# RobotBaseModule.net
KiCad netlist of a schematic drawn in EAGLE
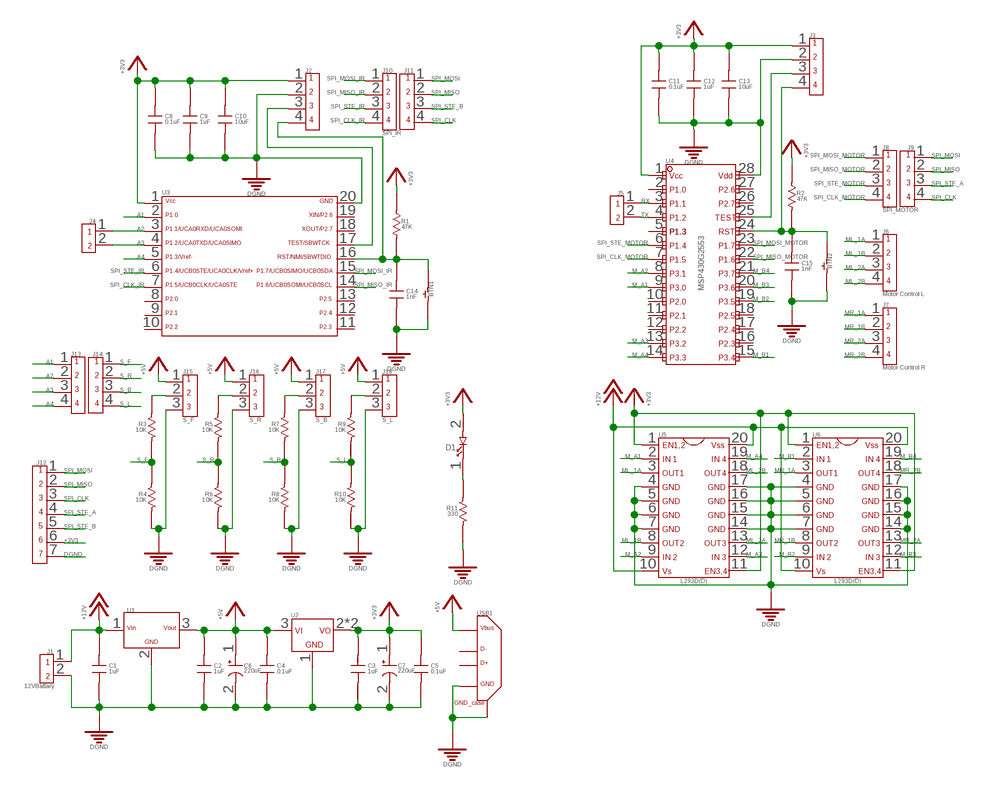
[diagram p0: schematic, sheet 1]

(export (version "E")
  (design (tool "Eeschema 10.0.6"))
  (components
    (comp (ref "BTN1")
      (value "BTN_NORMAL_OFF_6_3.5_SMD")
      (footprint "eagle-import:BTN_6_3.5_SMD")
      (libsource (lib "eagle-import") (part "BTN_NORMAL_OFF_6_3.5_SMD"))
    )
    (comp (ref "BTN2")
      (value "BTN_NORMAL_OFF_6_3.5_SMD")
      (footprint "eagle-import:BTN_6_3.5_SMD")
      (libsource (lib "eagle-import") (part "BTN_NORMAL_OFF_6_3.5_SMD"))
    )
    (comp (ref "C1")
      (value "1uF")
      (footprint "eagle-import:0805")
      (libsource (lib "eagle-import") (part "CAPACITOR_FIXED_0805"))
    )
    (comp (ref "C2")
      (value "1uF")
      (footprint "eagle-import:0805")
      (libsource (lib "eagle-import") (part "CAPACITOR_FIXED_0805"))
    )
    (comp (ref "C3")
      (value "1uF")
      (footprint "eagle-import:0805")
      (libsource (lib "eagle-import") (part "CAPACITOR_FIXED_0805"))
    )
    (comp (ref "C4")
      (value "0.1uF")
      (footprint "eagle-import:0805")
      (libsource (lib "eagle-import") (part "CAPACITOR_FIXED_0805"))
    )
    (comp (ref "C5")
      (value "0.1uF")
      (footprint "eagle-import:0805")
      (libsource (lib "eagle-import") (part "CAPACITOR_FIXED_0805"))
    )
    (comp (ref "C6")
      (value "220uF")
      (footprint "eagle-import:CAP_830_830")
      (libsource (lib "eagle-import") (part "CAPACITOR_POLARIZED_830_830"))
    )
    (comp (ref "C7")
      (value "220uF")
      (footprint "eagle-import:CAP_830_830")
      (libsource (lib "eagle-import") (part "CAPACITOR_POLARIZED_830_830"))
    )
    (comp (ref "C8")
      (value "0.1uF")
      (footprint "eagle-import:0805")
      (libsource (lib "eagle-import") (part "CAPACITOR_FIXED_0805"))
    )
    (comp (ref "C9")
      (value "1uF")
      (footprint "eagle-import:0805")
      (libsource (lib "eagle-import") (part "CAPACITOR_FIXED_0805"))
    )
    (comp (ref "C10")
      (value "10uF")
      (footprint "eagle-import:0805")
      (libsource (lib "eagle-import") (part "CAPACITOR_FIXED_0805"))
    )
    (comp (ref "C11")
      (value "0.1uF")
      (footprint "eagle-import:0805")
      (libsource (lib "eagle-import") (part "CAPACITOR_FIXED_0805"))
    )
    (comp (ref "C12")
      (value "1uF")
      (footprint "eagle-import:0805")
      (libsource (lib "eagle-import") (part "CAPACITOR_FIXED_0805"))
    )
    (comp (ref "C13")
      (value "10uF")
      (footprint "eagle-import:0805")
      (libsource (lib "eagle-import") (part "CAPACITOR_FIXED_0805"))
    )
    (comp (ref "C14")
      (value "1nF")
      (footprint "eagle-import:0805")
      (libsource (lib "eagle-import") (part "CAPACITOR_FIXED_0805"))
    )
    (comp (ref "C15")
      (value "1nF")
      (footprint "eagle-import:0805")
      (libsource (lib "eagle-import") (part "CAPACITOR_FIXED_0805"))
    )
    (comp (ref "D1")
      (value "LED_0805")
      (footprint "eagle-import:0805DIODE")
      (libsource (lib "eagle-import") (part "LED_0805"))
    )
    (comp (ref "J1")
      (value "12VBattary")
      (footprint "eagle-import:2PIN_TERMBLOCK_PITCH5.08MM")
      (libsource (lib "eagle-import") (part "2PIN_TERMBLOCK_PITCH5.08MM"))
    )
    (comp (ref "J2")
      (value "4PIN_HEADER_VERT_PITCH2.54MM_TH")
      (footprint "eagle-import:4PIN_HEADER_VERT_PITCH2.54MM_TH")
      (libsource (lib "eagle-import") (part "4PIN_HEADER_VERT_PITCH2.54MM_TH"))
    )
    (comp (ref "J3")
      (value "4PIN_HEADER_VERT_PITCH2.54MM_TH")
      (footprint "eagle-import:4PIN_HEADER_VERT_PITCH2.54MM_TH")
      (libsource (lib "eagle-import") (part "4PIN_HEADER_VERT_PITCH2.54MM_TH"))
    )
    (comp (ref "J4")
      (value "2PIN_HEADER_PITCH2.54MM_TH")
      (footprint "eagle-import:2PIN_HEADER_PITCH2.54MM_TH")
      (libsource (lib "eagle-import") (part "2PIN_HEADER_PITCH2.54MM_TH"))
    )
    (comp (ref "J5")
      (value "2PIN_HEADER_PITCH2.54MM_TH")
      (footprint "eagle-import:2PIN_HEADER_PITCH2.54MM_TH")
      (libsource (lib "eagle-import") (part "2PIN_HEADER_PITCH2.54MM_TH"))
    )
    (comp (ref "J6")
      (value "Motor Control L")
      (footprint "eagle-import:4PIN_HEADER_VERT_PITCH2.54MM_TH")
      (libsource (lib "eagle-import") (part "4PIN_HEADER_VERT_PITCH2.54MM_TH"))
    )
    (comp (ref "J7")
      (value "Motor Control R")
      (footprint "eagle-import:4PIN_HEADER_VERT_PITCH2.54MM_TH")
      (libsource (lib "eagle-import") (part "4PIN_HEADER_VERT_PITCH2.54MM_TH"))
    )
    (comp (ref "J8")
      (value "SPI_MOTOR")
      (footprint "eagle-import:4PIN_HEADER_PITCH2.54MM_TH")
      (libsource (lib "eagle-import") (part "4PIN_HEADER_PITCH2.54MM_TH"))
    )
    (comp (ref "J9")
      (value "4PIN_HEADER_PITCH2.54MM_TH")
      (footprint "eagle-import:4PIN_HEADER_PITCH2.54MM_TH")
      (libsource (lib "eagle-import") (part "4PIN_HEADER_PITCH2.54MM_TH"))
    )
    (comp (ref "J10")
      (value "SPI_IR")
      (footprint "eagle-import:4PIN_HEADER_PITCH2.54MM_TH")
      (libsource (lib "eagle-import") (part "4PIN_HEADER_PITCH2.54MM_TH"))
    )
    (comp (ref "J11")
      (value "4PIN_HEADER_PITCH2.54MM_TH")
      (footprint "eagle-import:4PIN_HEADER_PITCH2.54MM_TH")
      (libsource (lib "eagle-import") (part "4PIN_HEADER_PITCH2.54MM_TH"))
    )
    (comp (ref "J12")
      (value "7PIN_HEADER_VERT_PITCH2.54MM_TH")
      (footprint "eagle-import:7PIN_HEADER_VERT_PITCH2.54MM_TH")
      (libsource (lib "eagle-import") (part "7PIN_HEADER_VERT_PITCH2.54MM_TH"))
    )
    (comp (ref "J13")
      (value "4PIN_HEADER_PITCH2.54MM_TH")
      (footprint "eagle-import:4PIN_HEADER_PITCH2.54MM_TH")
      (libsource (lib "eagle-import") (part "4PIN_HEADER_PITCH2.54MM_TH"))
    )
    (comp (ref "J14")
      (value "4PIN_HEADER_PITCH2.54MM_TH")
      (footprint "eagle-import:4PIN_HEADER_PITCH2.54MM_TH")
      (libsource (lib "eagle-import") (part "4PIN_HEADER_PITCH2.54MM_TH"))
    )
    (comp (ref "J15")
      (value "S_F")
      (footprint "eagle-import:3PIN_HEADER_VERT_PITCH2.54MM_TH")
      (libsource (lib "eagle-import") (part "3PIN_HEADER_VERT_PITCH2.54MM_TH"))
    )
    (comp (ref "J16")
      (value "S_R")
      (footprint "eagle-import:3PIN_HEADER_VERT_PITCH2.54MM_TH")
      (libsource (lib "eagle-import") (part "3PIN_HEADER_VERT_PITCH2.54MM_TH"))
    )
    (comp (ref "J17")
      (value "S_B")
      (footprint "eagle-import:3PIN_HEADER_VERT_PITCH2.54MM_TH")
      (libsource (lib "eagle-import") (part "3PIN_HEADER_VERT_PITCH2.54MM_TH"))
    )
    (comp (ref "J18")
      (value "S_L")
      (footprint "eagle-import:3PIN_HEADER_VERT_PITCH2.54MM_TH")
      (libsource (lib "eagle-import") (part "3PIN_HEADER_VERT_PITCH2.54MM_TH"))
    )
    (comp (ref "R1")
      (value "47K")
      (footprint "eagle-import:0805")
      (libsource (lib "eagle-import") (part "RESISTOR_0805"))
    )
    (comp (ref "R2")
      (value "47K")
      (footprint "eagle-import:0805")
      (libsource (lib "eagle-import") (part "RESISTOR_0805"))
    )
    (comp (ref "R3")
      (value "10K")
      (footprint "eagle-import:0805")
      (libsource (lib "eagle-import") (part "RESISTOR_0805"))
    )
    (comp (ref "R4")
      (value "10K")
      (footprint "eagle-import:0805")
      (libsource (lib "eagle-import") (part "RESISTOR_0805"))
    )
    (comp (ref "R5")
      (value "10K")
      (footprint "eagle-import:0805")
      (libsource (lib "eagle-import") (part "RESISTOR_0805"))
    )
    (comp (ref "R6")
      (value "10K")
      (footprint "eagle-import:0805")
      (libsource (lib "eagle-import") (part "RESISTOR_0805"))
    )
    (comp (ref "R7")
      (value "10K")
      (footprint "eagle-import:0805")
      (libsource (lib "eagle-import") (part "RESISTOR_0805"))
    )
    (comp (ref "R8")
      (value "10K")
      (footprint "eagle-import:0805")
      (libsource (lib "eagle-import") (part "RESISTOR_0805"))
    )
    (comp (ref "R9")
      (value "10K")
      (footprint "eagle-import:0805")
      (libsource (lib "eagle-import") (part "RESISTOR_0805"))
    )
    (comp (ref "R10")
      (value "10K")
      (footprint "eagle-import:0805")
      (libsource (lib "eagle-import") (part "RESISTOR_0805"))
    )
    (comp (ref "R11")
      (value "330")
      (footprint "eagle-import:0805")
      (libsource (lib "eagle-import") (part "RESISTOR_0805"))
    )
    (comp (ref "U1")
      (value "V78-2000R")
      (footprint "eagle-import:V78-2000R")
      (libsource (lib "eagle-import") (part "V78-2000R"))
    )
    (comp (ref "U2")
      (value "LM1117_SOT-223-4")
      (footprint "eagle-import:SOT-233-4")
      (libsource (lib "eagle-import") (part "LM1117_SOT-223-4"))
    )
    (comp (ref "U3")
      (value "MSP430G2X53/G2X13_SSOP20")
      (footprint "eagle-import:SSOP-20")
      (libsource (lib "eagle-import") (part "MSP430G2X53/G2X13_SSOP20"))
    )
    (comp (ref "U4")
      (value "MSP430G2553")
      (footprint "eagle-import:TSSOP-28")
      (libsource (lib "eagle-import") (part "MSP430G2553_24IO_28PIN_TSSOP"))
    )
    (comp (ref "U5")
      (value "L293D(D)_ST_SMD")
      (footprint "eagle-import:SOIC_20")
      (libsource (lib "eagle-import") (part "L293D(D)_ST_SMD"))
    )
    (comp (ref "U6")
      (value "L293D(D)_ST_SMD")
      (footprint "eagle-import:SOIC_20")
      (libsource (lib "eagle-import") (part "L293D(D)_ST_SMD"))
    )
    (comp (ref "USB1")
      (value "USB-1.X/2.0-STANDARDTYPEA-TH")
      (footprint "eagle-import:USB-A-TH")
      (libsource (lib "eagle-import") (part "USB-1.X/2.0-STANDARDTYPEA-TH"))
    )
  )
  (nets
    (net (code "1") (name "+3V3") (class "Default")
      (node (ref "C10") (pin "1") (pinfunction "1_1") (pintype "passive"))
      (node (ref "C11") (pin "1") (pinfunction "1_1") (pintype "passive"))
      (node (ref "C12") (pin "1") (pinfunction "1_1") (pintype "passive"))
      (node (ref "C13") (pin "1") (pinfunction "1_1") (pintype "passive"))
      (node (ref "C3") (pin "1") (pinfunction "1_1") (pintype "passive"))
      (node (ref "C5") (pin "1") (pinfunction "1_1") (pintype "passive"))
      (node (ref "C7") (pin "1") (pinfunction "1_1") (pintype "passive"))
      (node (ref "C8") (pin "1") (pinfunction "1_1") (pintype "passive"))
      (node (ref "C9") (pin "1") (pinfunction "1_1") (pintype "passive"))
      (node (ref "D1") (pin "2") (pinfunction "2_2") (pintype "passive"))
      (node (ref "J12") (pin "6") (pinfunction "6_6") (pintype "passive"))
      (node (ref "J2") (pin "1") (pinfunction "1_1") (pintype "passive"))
      (node (ref "J3") (pin "1") (pinfunction "1_1") (pintype "passive"))
      (node (ref "R1") (pin "1") (pinfunction "1_1") (pintype "passive"))
      (node (ref "R2") (pin "1") (pinfunction "1_1") (pintype "passive"))
      (node (ref "U2") (pin "2") (pinfunction "VOUT_2") (pintype "passive"))
      (node (ref "U2") (pin "4") (pinfunction "VOUT_4") (pintype "passive"))
      (node (ref "U3") (pin "1") (pinfunction "1_1") (pintype "passive"))
      (node (ref "U4") (pin "1") (pinfunction "1_1") (pintype "passive"))
      (node (ref "U5") (pin "1") (pinfunction "1_1") (pintype "passive"))
      (node (ref "U5") (pin "11") (pinfunction "11_11") (pintype "passive"))
      (node (ref "U6") (pin "1") (pinfunction "1_1") (pintype "passive"))
      (node (ref "U6") (pin "11") (pinfunction "11_11") (pintype "passive"))
    )
    (net (code "2") (name "+5V") (class "Default")
      (node (ref "C2") (pin "1") (pinfunction "1_1") (pintype "passive"))
      (node (ref "C4") (pin "1") (pinfunction "1_1") (pintype "passive"))
      (node (ref "C6") (pin "1") (pinfunction "1_1") (pintype "passive"))
      (node (ref "J15") (pin "1") (pinfunction "1_1") (pintype "passive"))
      (node (ref "J16") (pin "1") (pinfunction "1_1") (pintype "passive"))
      (node (ref "J17") (pin "1") (pinfunction "1_1") (pintype "passive"))
      (node (ref "J18") (pin "1") (pinfunction "1_1") (pintype "passive"))
      (node (ref "U1") (pin "3") (pinfunction "VOUT_3") (pintype "passive"))
      (node (ref "U2") (pin "3") (pinfunction "VIN_3") (pintype "passive"))
      (node (ref "USB1") (pin "1") (pinfunction "VBUS_1") (pintype "passive"))
    )
    (net (code "3") (name "+12V") (class "Default")
      (node (ref "C1") (pin "1") (pinfunction "1_1") (pintype "passive"))
      (node (ref "J1") (pin "1") (pinfunction "1_1") (pintype "passive"))
      (node (ref "U1") (pin "1") (pinfunction "VIN_1") (pintype "passive"))
      (node (ref "U5") (pin "10") (pinfunction "10_10") (pintype "passive"))
      (node (ref "U5") (pin "20") (pinfunction "20_20") (pintype "passive"))
      (node (ref "U6") (pin "10") (pinfunction "10_10") (pintype "passive"))
      (node (ref "U6") (pin "20") (pinfunction "20_20") (pintype "passive"))
    )
    (net (code "4") (name "/A1") (class "Default")
      (node (ref "J13") (pin "1") (pinfunction "1_1") (pintype "passive"))
      (node (ref "U3") (pin "2") (pinfunction "2_2") (pintype "passive"))
    )
    (net (code "5") (name "/A2") (class "Default")
      (node (ref "J13") (pin "2") (pinfunction "2_2") (pintype "passive"))
      (node (ref "J4") (pin "1") (pinfunction "1_1") (pintype "passive"))
      (node (ref "U3") (pin "3") (pinfunction "3_3") (pintype "passive"))
    )
    (net (code "6") (name "/A3") (class "Default")
      (node (ref "J13") (pin "3") (pinfunction "3_3") (pintype "passive"))
      (node (ref "J4") (pin "2") (pinfunction "2_2") (pintype "passive"))
      (node (ref "U3") (pin "4") (pinfunction "4_4") (pintype "passive"))
    )
    (net (code "7") (name "/A4") (class "Default")
      (node (ref "J13") (pin "4") (pinfunction "4_4") (pintype "passive"))
      (node (ref "U3") (pin "5") (pinfunction "5_5") (pintype "passive"))
    )
    (net (code "8") (name "/ML_1A") (class "Default")
      (node (ref "J6") (pin "1") (pinfunction "1_1") (pintype "passive"))
      (node (ref "U5") (pin "3") (pinfunction "3_3") (pintype "passive"))
    )
    (net (code "9") (name "/ML_1B") (class "Default")
      (node (ref "J6") (pin "2") (pinfunction "2_2") (pintype "passive"))
      (node (ref "U5") (pin "8") (pinfunction "8_8") (pintype "passive"))
    )
    (net (code "10") (name "/ML_2A") (class "Default")
      (node (ref "J6") (pin "3") (pinfunction "3_3") (pintype "passive"))
      (node (ref "U5") (pin "13") (pinfunction "13_13") (pintype "passive"))
    )
    (net (code "11") (name "/ML_2B") (class "Default")
      (node (ref "J6") (pin "4") (pinfunction "4_4") (pintype "passive"))
      (node (ref "U5") (pin "18") (pinfunction "18_18") (pintype "passive"))
    )
    (net (code "12") (name "/MR_1A") (class "Default")
      (node (ref "J7") (pin "1") (pinfunction "1_1") (pintype "passive"))
      (node (ref "U6") (pin "3") (pinfunction "3_3") (pintype "passive"))
    )
    (net (code "13") (name "/MR_1B") (class "Default")
      (node (ref "J7") (pin "2") (pinfunction "2_2") (pintype "passive"))
      (node (ref "U6") (pin "8") (pinfunction "8_8") (pintype "passive"))
    )
    (net (code "14") (name "/MR_2A") (class "Default")
      (node (ref "J7") (pin "3") (pinfunction "3_3") (pintype "passive"))
      (node (ref "U6") (pin "13") (pinfunction "13_13") (pintype "passive"))
    )
    (net (code "15") (name "/MR_2B") (class "Default")
      (node (ref "J7") (pin "4") (pinfunction "4_4") (pintype "passive"))
      (node (ref "U6") (pin "18") (pinfunction "18_18") (pintype "passive"))
    )
    (net (code "16") (name "/M_A1") (class "Default")
      (node (ref "U4") (pin "9") (pinfunction "9_9") (pintype "passive"))
      (node (ref "U5") (pin "2") (pinfunction "2_2") (pintype "passive"))
    )
    (net (code "17") (name "/M_A2") (class "Default")
      (node (ref "U4") (pin "8") (pinfunction "8_8") (pintype "passive"))
      (node (ref "U5") (pin "9") (pinfunction "9_9") (pintype "passive"))
    )
    (net (code "18") (name "/M_A3") (class "Default")
      (node (ref "U4") (pin "13") (pinfunction "13_13") (pintype "passive"))
      (node (ref "U5") (pin "12") (pinfunction "12_12") (pintype "passive"))
    )
    (net (code "19") (name "/M_A4") (class "Default")
      (node (ref "U4") (pin "14") (pinfunction "14_14") (pintype "passive"))
      (node (ref "U5") (pin "19") (pinfunction "19_19") (pintype "passive"))
    )
    (net (code "20") (name "/M_B1") (class "Default")
      (node (ref "U4") (pin "15") (pinfunction "15_15") (pintype "passive"))
      (node (ref "U6") (pin "2") (pinfunction "2_2") (pintype "passive"))
    )
    (net (code "21") (name "/M_B2") (class "Default")
      (node (ref "U4") (pin "19") (pinfunction "19_19") (pintype "passive"))
      (node (ref "U6") (pin "9") (pinfunction "9_9") (pintype "passive"))
    )
    (net (code "22") (name "/M_B3") (class "Default")
      (node (ref "U4") (pin "20") (pinfunction "20_20") (pintype "passive"))
      (node (ref "U6") (pin "12") (pinfunction "12_12") (pintype "passive"))
    )
    (net (code "23") (name "/M_B4") (class "Default")
      (node (ref "U4") (pin "21") (pinfunction "21_21") (pintype "passive"))
      (node (ref "U6") (pin "19") (pinfunction "19_19") (pintype "passive"))
    )
    (net (code "24") (name "/RX") (class "Default")
      (node (ref "J5") (pin "1") (pinfunction "1_1") (pintype "passive"))
      (node (ref "U4") (pin "3") (pinfunction "3_3") (pintype "passive"))
    )
    (net (code "25") (name "/SPI_CLK") (class "Default")
      (node (ref "J11") (pin "4") (pinfunction "4_4") (pintype "passive"))
      (node (ref "J12") (pin "3") (pinfunction "3_3") (pintype "passive"))
      (node (ref "J9") (pin "4") (pinfunction "4_4") (pintype "passive"))
    )
    (net (code "26") (name "/SPI_CLK_IR") (class "Default")
      (node (ref "J10") (pin "4") (pinfunction "4_4") (pintype "passive"))
      (node (ref "U3") (pin "7") (pinfunction "7_7") (pintype "passive"))
    )
    (net (code "27") (name "/SPI_CLK_MOTOR") (class "Default")
      (node (ref "J8") (pin "4") (pinfunction "4_4") (pintype "passive"))
      (node (ref "U4") (pin "7") (pinfunction "7_7") (pintype "passive"))
    )
    (net (code "28") (name "/SPI_MISO") (class "Default")
      (node (ref "J11") (pin "2") (pinfunction "2_2") (pintype "passive"))
      (node (ref "J12") (pin "2") (pinfunction "2_2") (pintype "passive"))
      (node (ref "J9") (pin "2") (pinfunction "2_2") (pintype "passive"))
    )
    (net (code "29") (name "/SPI_MISO_IR") (class "Default")
      (node (ref "J10") (pin "2") (pinfunction "2_2") (pintype "passive"))
      (node (ref "U3") (pin "14") (pinfunction "14_14") (pintype "passive"))
    )
    (net (code "30") (name "/SPI_MISO_MOTOR") (class "Default")
      (node (ref "J8") (pin "2") (pinfunction "2_2") (pintype "passive"))
      (node (ref "U4") (pin "22") (pinfunction "22_22") (pintype "passive"))
    )
    (net (code "31") (name "/SPI_MOSI") (class "Default")
      (node (ref "J11") (pin "1") (pinfunction "1_1") (pintype "passive"))
      (node (ref "J12") (pin "1") (pinfunction "1_1") (pintype "passive"))
      (node (ref "J9") (pin "1") (pinfunction "1_1") (pintype "passive"))
    )
    (net (code "32") (name "/SPI_MOSI_IR") (class "Default")
      (node (ref "J10") (pin "1") (pinfunction "1_1") (pintype "passive"))
      (node (ref "U3") (pin "15") (pinfunction "15_15") (pintype "passive"))
    )
    (net (code "33") (name "/SPI_MOSI_MOTOR") (class "Default")
      (node (ref "J8") (pin "1") (pinfunction "1_1") (pintype "passive"))
      (node (ref "U4") (pin "23") (pinfunction "23_23") (pintype "passive"))
    )
    (net (code "34") (name "/SPI_STE_A") (class "Default")
      (node (ref "J12") (pin "4") (pinfunction "4_4") (pintype "passive"))
      (node (ref "J9") (pin "3") (pinfunction "3_3") (pintype "passive"))
    )
    (net (code "35") (name "/SPI_STE_B") (class "Default")
      (node (ref "J11") (pin "3") (pinfunction "3_3") (pintype "passive"))
      (node (ref "J12") (pin "5") (pinfunction "5_5") (pintype "passive"))
    )
    (net (code "36") (name "/SPI_STE_IR") (class "Default")
      (node (ref "J10") (pin "3") (pinfunction "3_3") (pintype "passive"))
      (node (ref "U3") (pin "6") (pinfunction "6_6") (pintype "passive"))
    )
    (net (code "37") (name "/SPI_STE_MOTOR") (class "Default")
      (node (ref "J8") (pin "3") (pinfunction "3_3") (pintype "passive"))
      (node (ref "U4") (pin "6") (pinfunction "6_6") (pintype "passive"))
    )
    (net (code "38") (name "/S_B") (class "Default")
      (node (ref "J14") (pin "3") (pinfunction "3_3") (pintype "passive"))
      (node (ref "R7") (pin "2") (pinfunction "2_2") (pintype "passive"))
      (node (ref "R8") (pin "1") (pinfunction "1_1") (pintype "passive"))
    )
    (net (code "39") (name "/S_F") (class "Default")
      (node (ref "J14") (pin "1") (pinfunction "1_1") (pintype "passive"))
      (node (ref "R3") (pin "2") (pinfunction "2_2") (pintype "passive"))
      (node (ref "R4") (pin "1") (pinfunction "1_1") (pintype "passive"))
    )
    (net (code "40") (name "/S_L") (class "Default")
      (node (ref "J14") (pin "4") (pinfunction "4_4") (pintype "passive"))
      (node (ref "R10") (pin "1") (pinfunction "1_1") (pintype "passive"))
      (node (ref "R9") (pin "2") (pinfunction "2_2") (pintype "passive"))
    )
    (net (code "41") (name "/S_R") (class "Default")
      (node (ref "J14") (pin "2") (pinfunction "2_2") (pintype "passive"))
      (node (ref "R5") (pin "2") (pinfunction "2_2") (pintype "passive"))
      (node (ref "R6") (pin "1") (pinfunction "1_1") (pintype "passive"))
    )
    (net (code "42") (name "/TX") (class "Default")
      (node (ref "J5") (pin "2") (pinfunction "2_2") (pintype "passive"))
      (node (ref "U4") (pin "4") (pinfunction "4_4") (pintype "passive"))
    )
    (net (code "43") (name "DGND") (class "Default")
      (node (ref "BTN1") (pin "2") (pinfunction "2_2") (pintype "passive"))
      (node (ref "BTN2") (pin "2") (pinfunction "2_2") (pintype "passive"))
      (node (ref "C1") (pin "2") (pinfunction "2_2") (pintype "passive"))
      (node (ref "C10") (pin "2") (pinfunction "2_2") (pintype "passive"))
      (node (ref "C11") (pin "2") (pinfunction "2_2") (pintype "passive"))
      (node (ref "C12") (pin "2") (pinfunction "2_2") (pintype "passive"))
      (node (ref "C13") (pin "2") (pinfunction "2_2") (pintype "passive"))
      (node (ref "C14") (pin "2") (pinfunction "2_2") (pintype "passive"))
      (node (ref "C15") (pin "2") (pinfunction "2_2") (pintype "passive"))
      (node (ref "C2") (pin "2") (pinfunction "2_2") (pintype "passive"))
      (node (ref "C3") (pin "2") (pinfunction "2_2") (pintype "passive"))
      (node (ref "C4") (pin "2") (pinfunction "2_2") (pintype "passive"))
      (node (ref "C5") (pin "2") (pinfunction "2_2") (pintype "passive"))
      (node (ref "C6") (pin "2") (pinfunction "2_2") (pintype "passive"))
      (node (ref "C7") (pin "2") (pinfunction "2_2") (pintype "passive"))
      (node (ref "C8") (pin "2") (pinfunction "2_2") (pintype "passive"))
      (node (ref "C9") (pin "2") (pinfunction "2_2") (pintype "passive"))
      (node (ref "J1") (pin "2") (pinfunction "2_2") (pintype "passive"))
      (node (ref "J12") (pin "7") (pinfunction "7_7") (pintype "passive"))
      (node (ref "J15") (pin "3") (pinfunction "3_3") (pintype "passive"))
      (node (ref "J16") (pin "3") (pinfunction "3_3") (pintype "passive"))
      (node (ref "J17") (pin "3") (pinfunction "3_3") (pintype "passive"))
      (node (ref "J18") (pin "3") (pinfunction "3_3") (pintype "passive"))
      (node (ref "J2") (pin "2") (pinfunction "2_2") (pintype "passive"))
      (node (ref "J3") (pin "2") (pinfunction "2_2") (pintype "passive"))
      (node (ref "R10") (pin "2") (pinfunction "2_2") (pintype "passive"))
      (node (ref "R11") (pin "2") (pinfunction "2_2") (pintype "passive"))
      (node (ref "R4") (pin "2") (pinfunction "2_2") (pintype "passive"))
      (node (ref "R6") (pin "2") (pinfunction "2_2") (pintype "passive"))
      (node (ref "R8") (pin "2") (pinfunction "2_2") (pintype "passive"))
      (node (ref "U1") (pin "2") (pinfunction "GND_2") (pintype "passive"))
      (node (ref "U2") (pin "1") (pinfunction "GND_1") (pintype "passive"))
      (node (ref "U3") (pin "20") (pinfunction "20_20") (pintype "passive"))
      (node (ref "U4") (pin "28") (pinfunction "P$7_28") (pintype "passive"))
      (node (ref "U5") (pin "14") (pinfunction "14_14") (pintype "passive"))
      (node (ref "U5") (pin "15") (pinfunction "15_15") (pintype "passive"))
      (node (ref "U5") (pin "16") (pinfunction "16_16") (pintype "passive"))
      (node (ref "U5") (pin "17") (pinfunction "17_17") (pintype "passive"))
      (node (ref "U5") (pin "4") (pinfunction "4_4") (pintype "passive"))
      (node (ref "U5") (pin "5") (pinfunction "5_5") (pintype "passive"))
      (node (ref "U5") (pin "6") (pinfunction "6_6") (pintype "passive"))
      (node (ref "U5") (pin "7") (pinfunction "7_7") (pintype "passive"))
      (node (ref "U6") (pin "14") (pinfunction "14_14") (pintype "passive"))
      (node (ref "U6") (pin "15") (pinfunction "15_15") (pintype "passive"))
      (node (ref "U6") (pin "16") (pinfunction "16_16") (pintype "passive"))
      (node (ref "U6") (pin "17") (pinfunction "17_17") (pintype "passive"))
      (node (ref "U6") (pin "4") (pinfunction "4_4") (pintype "passive"))
      (node (ref "U6") (pin "5") (pinfunction "5_5") (pintype "passive"))
      (node (ref "U6") (pin "6") (pinfunction "6_6") (pintype "passive"))
      (node (ref "U6") (pin "7") (pinfunction "7_7") (pintype "passive"))
      (node (ref "USB1") (pin "4") (pinfunction "GND_4") (pintype "passive"))
      (node (ref "USB1") (pin "CASE1") (pinfunction "GND_CASE_CASE1") (pintype "passive"))
      (node (ref "USB1") (pin "CASE2") (pinfunction "GND_CASE_CASE2") (pintype "passive"))
    )
    (net (code "44") (name "Net-(BTN1-Pad1)") (class "Default")
      (node (ref "BTN1") (pin "1") (pinfunction "1_1") (pintype "passive"))
      (node (ref "C14") (pin "1") (pinfunction "1_1") (pintype "passive"))
      (node (ref "J2") (pin "4") (pinfunction "4_4") (pintype "passive"))
      (node (ref "R1") (pin "2") (pinfunction "2_2") (pintype "passive"))
      (node (ref "U3") (pin "16") (pinfunction "16_16") (pintype "passive"))
    )
    (net (code "45") (name "Net-(BTN2-Pad1)") (class "Default")
      (node (ref "BTN2") (pin "1") (pinfunction "1_1") (pintype "passive"))
      (node (ref "C15") (pin "1") (pinfunction "1_1") (pintype "passive"))
      (node (ref "J3") (pin "4") (pinfunction "4_4") (pintype "passive"))
      (node (ref "R2") (pin "2") (pinfunction "2_2") (pintype "passive"))
      (node (ref "U4") (pin "24") (pinfunction "24_24") (pintype "passive"))
    )
    (net (code "46") (name "Net-(D1-Pad1)") (class "Default")
      (node (ref "D1") (pin "1") (pinfunction "1_1") (pintype "passive"))
      (node (ref "R11") (pin "1") (pinfunction "1_1") (pintype "passive"))
    )
    (net (code "47") (name "Net-(J2-Pad3)") (class "Default")
      (node (ref "J2") (pin "3") (pinfunction "3_3") (pintype "passive"))
      (node (ref "U3") (pin "17") (pinfunction "17_17") (pintype "passive"))
    )
    (net (code "48") (name "Net-(J3-Pad3)") (class "Default")
      (node (ref "J3") (pin "3") (pinfunction "3_3") (pintype "passive"))
      (node (ref "U4") (pin "25") (pinfunction "25_25") (pintype "passive"))
    )
    (net (code "49") (name "Net-(J15-Pad2)") (class "Default")
      (node (ref "J15") (pin "2") (pinfunction "2_2") (pintype "passive"))
      (node (ref "R3") (pin "1") (pinfunction "1_1") (pintype "passive"))
    )
    (net (code "50") (name "Net-(J16-Pad2)") (class "Default")
      (node (ref "J16") (pin "2") (pinfunction "2_2") (pintype "passive"))
      (node (ref "R5") (pin "1") (pinfunction "1_1") (pintype "passive"))
    )
    (net (code "51") (name "Net-(J17-Pad2)") (class "Default")
      (node (ref "J17") (pin "2") (pinfunction "2_2") (pintype "passive"))
      (node (ref "R7") (pin "1") (pinfunction "1_1") (pintype "passive"))
    )
    (net (code "52") (name "Net-(J18-Pad2)") (class "Default")
      (node (ref "J18") (pin "2") (pinfunction "2_2") (pintype "passive"))
      (node (ref "R9") (pin "1") (pinfunction "1_1") (pintype "passive"))
    )
    (net (code "53") (name "unconnected-(U3-Pad8)") (class "Default")
      (node (ref "U3") (pin "8") (pinfunction "8_8") (pintype "passive"))
    )
    (net (code "54") (name "unconnected-(U3-Pad9)") (class "Default")
      (node (ref "U3") (pin "9") (pinfunction "9_9") (pintype "passive"))
    )
    (net (code "55") (name "unconnected-(U3-Pad10)") (class "Default")
      (node (ref "U3") (pin "10") (pinfunction "10_10") (pintype "passive"))
    )
    (net (code "56") (name "unconnected-(U3-Pad11)") (class "Default")
      (node (ref "U3") (pin "11") (pinfunction "11_11") (pintype "passive"))
    )
    (net (code "57") (name "unconnected-(U3-Pad12)") (class "Default")
      (node (ref "U3") (pin "12") (pinfunction "12_12") (pintype "passive"))
    )
    (net (code "58") (name "unconnected-(U3-Pad13)") (class "Default")
      (node (ref "U3") (pin "13") (pinfunction "13_13") (pintype "passive"))
    )
    (net (code "59") (name "unconnected-(U3-Pad18)") (class "Default")
      (node (ref "U3") (pin "18") (pinfunction "18_18") (pintype "passive"))
    )
    (net (code "60") (name "unconnected-(U3-Pad19)") (class "Default")
      (node (ref "U3") (pin "19") (pinfunction "19_19") (pintype "passive"))
    )
    (net (code "61") (name "unconnected-(U4-Pad2)") (class "Default")
      (node (ref "U4") (pin "2") (pinfunction "2_2") (pintype "passive"))
    )
    (net (code "62") (name "unconnected-(U4-Pad5)") (class "Default")
      (node (ref "U4") (pin "5") (pinfunction "5_5") (pintype "passive"))
    )
    (net (code "63") (name "unconnected-(U4-Pad10)") (class "Default")
      (node (ref "U4") (pin "10") (pinfunction "10_10") (pintype "passive"))
    )
    (net (code "64") (name "unconnected-(U4-Pad11)") (class "Default")
      (node (ref "U4") (pin "11") (pinfunction "11_11") (pintype "passive"))
    )
    (net (code "65") (name "unconnected-(U4-Pad12)") (class "Default")
      (node (ref "U4") (pin "12") (pinfunction "12_12") (pintype "passive"))
    )
    (net (code "66") (name "unconnected-(U4-Pad16)") (class "Default")
      (node (ref "U4") (pin "16") (pinfunction "16_16") (pintype "passive"))
    )
    (net (code "67") (name "unconnected-(U4-Pad17)") (class "Default")
      (node (ref "U4") (pin "17") (pinfunction "17_17") (pintype "passive"))
    )
    (net (code "68") (name "unconnected-(U4-Pad18)") (class "Default")
      (node (ref "U4") (pin "18") (pinfunction "18_18") (pintype "passive"))
    )
    (net (code "69") (name "unconnected-(U4-Pad26)") (class "Default")
      (node (ref "U4") (pin "26") (pinfunction "26_26") (pintype "passive"))
    )
    (net (code "70") (name "unconnected-(U4-Pad27)") (class "Default")
      (node (ref "U4") (pin "27") (pinfunction "27_27") (pintype "passive"))
    )
    (net (code "71") (name "unconnected-(USB1-D+-Pad3)") (class "Default")
      (node (ref "USB1") (pin "3") (pinfunction "D+_3") (pintype "passive"))
    )
    (net (code "72") (name "unconnected-(USB1-D--Pad2)") (class "Default")
      (node (ref "USB1") (pin "2") (pinfunction "D-_2") (pintype "passive"))
    )
  )
)
